# Syno_Ver1.net
KiCad netlist of a schematic drawn in EAGLE
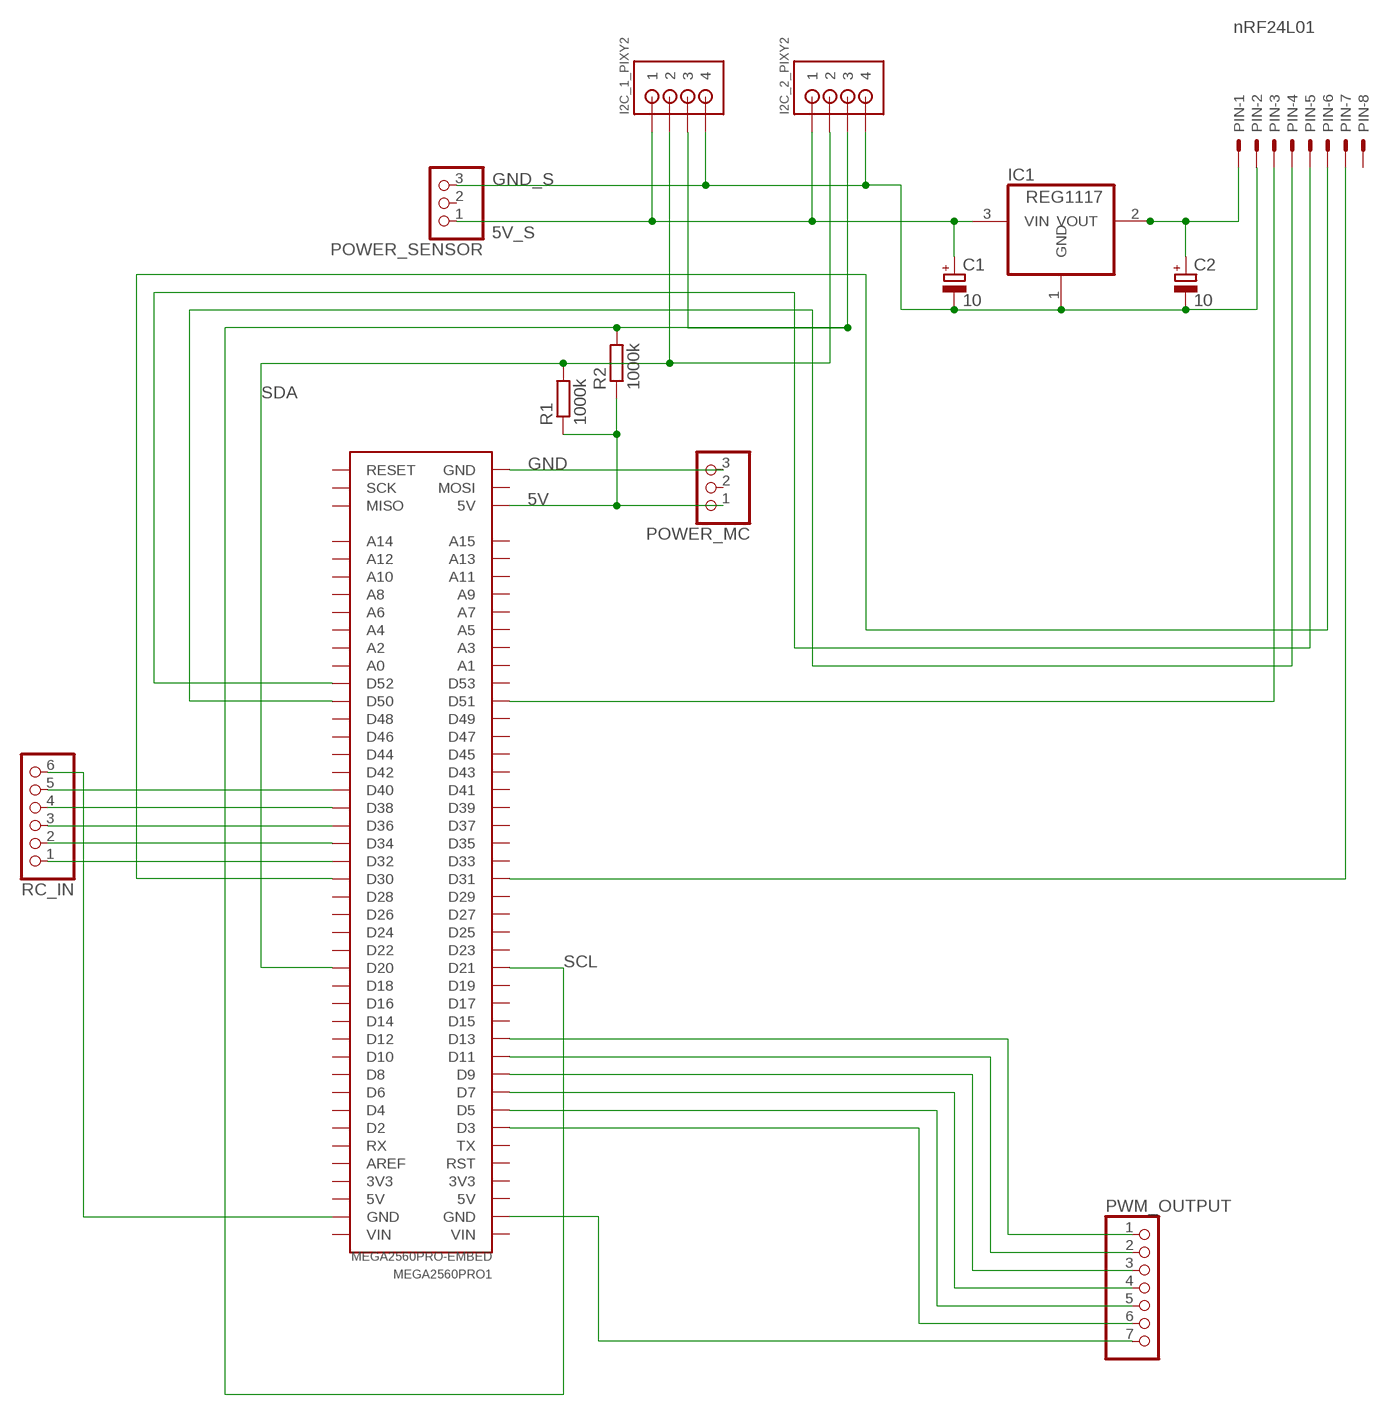
[diagram p0: schematic, sheet 1]

(export (version "E")
  (design (tool "Eeschema 10.0.6"))
  (components
    (comp (ref "C1")
      (value "10")
      (footprint "eagle-import:E1,8-4")
      (libsource (lib "eagle-import") (part "CPOL-EUE1.8-4"))
    )
    (comp (ref "C2")
      (value "10")
      (footprint "eagle-import:E1,8-4")
      (libsource (lib "eagle-import") (part "CPOL-EUE1.8-4"))
    )
    (comp (ref "I2C_1_PIXY2")
      (value "JST-PH_4-PIN_HEADER")
      (footprint "eagle-import:JST_B4B-PH_HEADER")
      (libsource (lib "eagle-import") (part "JST-PH_4-PIN_HEADER"))
    )
    (comp (ref "I2C_2_PIXY2")
      (value "JST-PH_4-PIN_HEADER")
      (footprint "eagle-import:JST_B4B-PH_HEADER")
      (libsource (lib "eagle-import") (part "JST-PH_4-PIN_HEADER"))
    )
    (comp (ref "IC1")
      (value "REG1117")
      (footprint "eagle-import:SOT223")
      (libsource (lib "eagle-import") (part "REG1117"))
    )
    (comp (ref "MEGA2560PRO1")
      (value "MEGA2560PRO-EMBED")
      (footprint "eagle-import:MEGA2560PRO-EMBED")
      (libsource (lib "eagle-import") (part "MEGA2560PRO-EMBED"))
    )
    (comp (ref "PIN")
      (value "nRF24L01")
      (footprint "eagle-import:JST-XH-08-PACKAGE-ROUND-PAD")
      (libsource (lib "eagle-import") (part "JST-XH-08-PIN-ROUND-PAD"))
    )
    (comp (ref "POWER_MC")
      (value "PINHD-1X3/90")
      (footprint "eagle-import:1X03_90")
      (libsource (lib "eagle-import") (part "PINHD-1X3/90"))
    )
    (comp (ref "POWER_SENSOR")
      (value "PINHD-1X3/90")
      (footprint "eagle-import:1X03_90")
      (libsource (lib "eagle-import") (part "PINHD-1X3/90"))
    )
    (comp (ref "PWM_OUTPUT")
      (value "PINHD-1X7/90")
      (footprint "eagle-import:1X07_90")
      (libsource (lib "eagle-import") (part "PINHD-1X7/90"))
    )
    (comp (ref "R1")
      (value "1000k")
      (footprint "eagle-import:0204_5")
      (libsource (lib "eagle-import") (part "R-EU_0204/5"))
    )
    (comp (ref "R2")
      (value "1000k")
      (footprint "eagle-import:0204_5")
      (libsource (lib "eagle-import") (part "R-EU_0204/5"))
    )
    (comp (ref "RC_IN")
      (value "PINHD-1X6/90")
      (footprint "eagle-import:1X06_90")
      (libsource (lib "eagle-import") (part "PINHD-1X6/90"))
    )
  )
  (nets
    (net (code "1") (name "/5V") (class "Default")
      (node (ref "MEGA2560PRO1") (pin "5V@3") (pinfunction "5V_5V@3") (pintype "bidirectional"))
      (node (ref "POWER_MC") (pin "1") (pinfunction "1_1") (pintype "passive"))
      (node (ref "R1") (pin "1") (pinfunction "1_1") (pintype "passive"))
      (node (ref "R2") (pin "1") (pinfunction "1_1") (pintype "passive"))
    )
    (net (code "2") (name "/5V_S") (class "Default")
      (node (ref "C1") (pin "+") (pinfunction "+_+") (pintype "passive"))
      (node (ref "I2C_1_PIXY2") (pin "P1") (pinfunction "1_P1") (pintype "bidirectional"))
      (node (ref "I2C_2_PIXY2") (pin "P1") (pinfunction "1_P1") (pintype "bidirectional"))
      (node (ref "IC1") (pin "3") (pinfunction "VIN_3") (pintype "input"))
      (node (ref "POWER_SENSOR") (pin "1") (pinfunction "1_1") (pintype "passive"))
    )
    (net (code "3") (name "/GND") (class "Default")
      (node (ref "MEGA2560PRO1") (pin "GND@3") (pinfunction "GND_GND@3") (pintype "bidirectional"))
      (node (ref "POWER_MC") (pin "3") (pinfunction "3_3") (pintype "passive"))
    )
    (net (code "4") (name "/GND_S") (class "Default")
      (node (ref "C1") (pin "-") (pinfunction "-_-") (pintype "passive"))
      (node (ref "C2") (pin "-") (pinfunction "-_-") (pintype "passive"))
      (node (ref "I2C_1_PIXY2") (pin "P4") (pinfunction "4_P4") (pintype "bidirectional"))
      (node (ref "I2C_2_PIXY2") (pin "P4") (pinfunction "4_P4") (pintype "bidirectional"))
      (node (ref "IC1") (pin "1") (pinfunction "GND_1") (pintype "power_in"))
      (node (ref "PIN") (pin "2") (pinfunction "S_2") (pintype "passive"))
      (node (ref "POWER_SENSOR") (pin "3") (pinfunction "3_3") (pintype "passive"))
    )
    (net (code "5") (name "/SCL") (class "Default")
      (node (ref "I2C_1_PIXY2") (pin "P3") (pinfunction "3_P3") (pintype "bidirectional"))
      (node (ref "I2C_2_PIXY2") (pin "P3") (pinfunction "3_P3") (pintype "bidirectional"))
      (node (ref "MEGA2560PRO1") (pin "D21") (pinfunction "D21_D21") (pintype "bidirectional"))
      (node (ref "R2") (pin "2") (pinfunction "2_2") (pintype "passive"))
    )
    (net (code "6") (name "/SDA") (class "Default")
      (node (ref "I2C_1_PIXY2") (pin "P2") (pinfunction "2_P2") (pintype "bidirectional"))
      (node (ref "I2C_2_PIXY2") (pin "P2") (pinfunction "2_P2") (pintype "bidirectional"))
      (node (ref "MEGA2560PRO1") (pin "D20") (pinfunction "D20_D20") (pintype "bidirectional"))
      (node (ref "R1") (pin "2") (pinfunction "2_2") (pintype "passive"))
    )
    (net (code "7") (name "Net-(IC1-VOUT)") (class "Default")
      (node (ref "C2") (pin "+") (pinfunction "+_+") (pintype "passive"))
      (node (ref "IC1") (pin "2") (pinfunction "VOUT_2") (pintype "output"))
      (node (ref "PIN") (pin "1") (pinfunction "S_1") (pintype "passive"))
    )
    (net (code "8") (name "Net-(MEGA2560PRO1-GND-PadGND@1)") (class "Default")
      (node (ref "MEGA2560PRO1") (pin "GND@1") (pinfunction "GND_GND@1") (pintype "bidirectional"))
      (node (ref "PWM_OUTPUT") (pin "7") (pinfunction "7_7") (pintype "passive"))
    )
    (net (code "9") (name "Net-(MEGA2560PRO1-GND-PadGND@2)") (class "Default")
      (node (ref "MEGA2560PRO1") (pin "GND@2") (pinfunction "GND_GND@2") (pintype "bidirectional"))
      (node (ref "RC_IN") (pin "6") (pinfunction "6_6") (pintype "passive"))
    )
    (net (code "10") (name "Net-(MEGA2560PRO1-PadD3)") (class "Default")
      (node (ref "MEGA2560PRO1") (pin "D3") (pinfunction "D3_D3") (pintype "bidirectional"))
      (node (ref "PWM_OUTPUT") (pin "6") (pinfunction "6_6") (pintype "passive"))
    )
    (net (code "11") (name "Net-(MEGA2560PRO1-PadD5)") (class "Default")
      (node (ref "MEGA2560PRO1") (pin "D5") (pinfunction "D5_D5") (pintype "bidirectional"))
      (node (ref "PWM_OUTPUT") (pin "5") (pinfunction "5_5") (pintype "passive"))
    )
    (net (code "12") (name "Net-(MEGA2560PRO1-PadD7)") (class "Default")
      (node (ref "MEGA2560PRO1") (pin "D7") (pinfunction "D7_D7") (pintype "bidirectional"))
      (node (ref "PWM_OUTPUT") (pin "4") (pinfunction "4_4") (pintype "passive"))
    )
    (net (code "13") (name "Net-(MEGA2560PRO1-PadD9)") (class "Default")
      (node (ref "MEGA2560PRO1") (pin "D9") (pinfunction "D9_D9") (pintype "bidirectional"))
      (node (ref "PWM_OUTPUT") (pin "3") (pinfunction "3_3") (pintype "passive"))
    )
    (net (code "14") (name "Net-(MEGA2560PRO1-PadD11)") (class "Default")
      (node (ref "MEGA2560PRO1") (pin "D11") (pinfunction "D11_D11") (pintype "bidirectional"))
      (node (ref "PWM_OUTPUT") (pin "2") (pinfunction "2_2") (pintype "passive"))
    )
    (net (code "15") (name "Net-(MEGA2560PRO1-PadD13)") (class "Default")
      (node (ref "MEGA2560PRO1") (pin "D13") (pinfunction "D13_D13") (pintype "bidirectional"))
      (node (ref "PWM_OUTPUT") (pin "1") (pinfunction "1_1") (pintype "passive"))
    )
    (net (code "16") (name "Net-(MEGA2560PRO1-PadD32)") (class "Default")
      (node (ref "MEGA2560PRO1") (pin "D32") (pinfunction "D32_D32") (pintype "bidirectional"))
      (node (ref "RC_IN") (pin "1") (pinfunction "1_1") (pintype "passive"))
    )
    (net (code "17") (name "Net-(MEGA2560PRO1-PadD34)") (class "Default")
      (node (ref "MEGA2560PRO1") (pin "D34") (pinfunction "D34_D34") (pintype "bidirectional"))
      (node (ref "RC_IN") (pin "2") (pinfunction "2_2") (pintype "passive"))
    )
    (net (code "18") (name "Net-(MEGA2560PRO1-PadD36)") (class "Default")
      (node (ref "MEGA2560PRO1") (pin "D36") (pinfunction "D36_D36") (pintype "bidirectional"))
      (node (ref "RC_IN") (pin "3") (pinfunction "3_3") (pintype "passive"))
    )
    (net (code "19") (name "Net-(MEGA2560PRO1-PadD38)") (class "Default")
      (node (ref "MEGA2560PRO1") (pin "D38") (pinfunction "D38_D38") (pintype "bidirectional"))
      (node (ref "RC_IN") (pin "4") (pinfunction "4_4") (pintype "passive"))
    )
    (net (code "20") (name "Net-(MEGA2560PRO1-PadD40)") (class "Default")
      (node (ref "MEGA2560PRO1") (pin "D40") (pinfunction "D40_D40") (pintype "bidirectional"))
      (node (ref "RC_IN") (pin "5") (pinfunction "5_5") (pintype "passive"))
    )
    (net (code "21") (name "Net-(PINC-S)") (class "Default")
      (node (ref "MEGA2560PRO1") (pin "D51") (pinfunction "D51_D51") (pintype "bidirectional"))
      (node (ref "PIN") (pin "3") (pinfunction "S_3") (pintype "passive"))
    )
    (net (code "22") (name "Net-(PIND-S)") (class "Default")
      (node (ref "MEGA2560PRO1") (pin "D50") (pinfunction "D50_D50") (pintype "bidirectional"))
      (node (ref "PIN") (pin "4") (pinfunction "S_4") (pintype "passive"))
    )
    (net (code "23") (name "Net-(PINE-S)") (class "Default")
      (node (ref "MEGA2560PRO1") (pin "D52") (pinfunction "D52_D52") (pintype "bidirectional"))
      (node (ref "PIN") (pin "5") (pinfunction "S_5") (pintype "passive"))
    )
    (net (code "24") (name "Net-(PINF-S)") (class "Default")
      (node (ref "MEGA2560PRO1") (pin "D30") (pinfunction "D30_D30") (pintype "bidirectional"))
      (node (ref "PIN") (pin "6") (pinfunction "S_6") (pintype "passive"))
    )
    (net (code "25") (name "Net-(PING-S)") (class "Default")
      (node (ref "MEGA2560PRO1") (pin "D31") (pinfunction "D31_D31") (pintype "bidirectional"))
      (node (ref "PIN") (pin "7") (pinfunction "S_7") (pintype "passive"))
    )
    (net (code "26") (name "unconnected-(MEGA2560PRO1-3V3-Pad3V3@1)") (class "Default")
      (node (ref "MEGA2560PRO1") (pin "3V3@1") (pinfunction "3V3_3V3@1") (pintype "bidirectional"))
    )
    (net (code "27") (name "unconnected-(MEGA2560PRO1-3V3-Pad3V3@2)") (class "Default")
      (node (ref "MEGA2560PRO1") (pin "3V3@2") (pinfunction "3V3_3V3@2") (pintype "bidirectional"))
    )
    (net (code "28") (name "unconnected-(MEGA2560PRO1-5V-Pad5V@1)") (class "Default")
      (node (ref "MEGA2560PRO1") (pin "5V@1") (pinfunction "5V_5V@1") (pintype "bidirectional"))
    )
    (net (code "29") (name "unconnected-(MEGA2560PRO1-5V-Pad5V@2)") (class "Default")
      (node (ref "MEGA2560PRO1") (pin "5V@2") (pinfunction "5V_5V@2") (pintype "bidirectional"))
    )
    (net (code "30") (name "unconnected-(MEGA2560PRO1-PadA0)") (class "Default")
      (node (ref "MEGA2560PRO1") (pin "A0") (pinfunction "A0_A0") (pintype "bidirectional"))
    )
    (net (code "31") (name "unconnected-(MEGA2560PRO1-PadA1)") (class "Default")
      (node (ref "MEGA2560PRO1") (pin "A1") (pinfunction "A1_A1") (pintype "bidirectional"))
    )
    (net (code "32") (name "unconnected-(MEGA2560PRO1-PadA2)") (class "Default")
      (node (ref "MEGA2560PRO1") (pin "A2") (pinfunction "A2_A2") (pintype "bidirectional"))
    )
    (net (code "33") (name "unconnected-(MEGA2560PRO1-PadA3)") (class "Default")
      (node (ref "MEGA2560PRO1") (pin "A3") (pinfunction "A3_A3") (pintype "bidirectional"))
    )
    (net (code "34") (name "unconnected-(MEGA2560PRO1-PadA4)") (class "Default")
      (node (ref "MEGA2560PRO1") (pin "A4") (pinfunction "A4_A4") (pintype "bidirectional"))
    )
    (net (code "35") (name "unconnected-(MEGA2560PRO1-PadA5)") (class "Default")
      (node (ref "MEGA2560PRO1") (pin "A5") (pinfunction "A5_A5") (pintype "bidirectional"))
    )
    (net (code "36") (name "unconnected-(MEGA2560PRO1-PadA6)") (class "Default")
      (node (ref "MEGA2560PRO1") (pin "A6") (pinfunction "A6_A6") (pintype "bidirectional"))
    )
    (net (code "37") (name "unconnected-(MEGA2560PRO1-PadA7)") (class "Default")
      (node (ref "MEGA2560PRO1") (pin "A7") (pinfunction "A7_A7") (pintype "bidirectional"))
    )
    (net (code "38") (name "unconnected-(MEGA2560PRO1-PadA8)") (class "Default")
      (node (ref "MEGA2560PRO1") (pin "A8") (pinfunction "A8_A8") (pintype "bidirectional"))
    )
    (net (code "39") (name "unconnected-(MEGA2560PRO1-PadA9)") (class "Default")
      (node (ref "MEGA2560PRO1") (pin "A9") (pinfunction "A9_A9") (pintype "bidirectional"))
    )
    (net (code "40") (name "unconnected-(MEGA2560PRO1-PadA10)") (class "Default")
      (node (ref "MEGA2560PRO1") (pin "A10") (pinfunction "A10_A10") (pintype "bidirectional"))
    )
    (net (code "41") (name "unconnected-(MEGA2560PRO1-PadA11)") (class "Default")
      (node (ref "MEGA2560PRO1") (pin "A11") (pinfunction "A11_A11") (pintype "bidirectional"))
    )
    (net (code "42") (name "unconnected-(MEGA2560PRO1-PadA12)") (class "Default")
      (node (ref "MEGA2560PRO1") (pin "A12") (pinfunction "A12_A12") (pintype "bidirectional"))
    )
    (net (code "43") (name "unconnected-(MEGA2560PRO1-PadA13)") (class "Default")
      (node (ref "MEGA2560PRO1") (pin "A13") (pinfunction "A13_A13") (pintype "bidirectional"))
    )
    (net (code "44") (name "unconnected-(MEGA2560PRO1-PadA14)") (class "Default")
      (node (ref "MEGA2560PRO1") (pin "A14") (pinfunction "A14_A14") (pintype "bidirectional"))
    )
    (net (code "45") (name "unconnected-(MEGA2560PRO1-PadA15)") (class "Default")
      (node (ref "MEGA2560PRO1") (pin "A15") (pinfunction "A15_A15") (pintype "bidirectional"))
    )
    (net (code "46") (name "unconnected-(MEGA2560PRO1-PadAREF)") (class "Default")
      (node (ref "MEGA2560PRO1") (pin "AREF") (pinfunction "AREF_AREF") (pintype "bidirectional"))
    )
    (net (code "47") (name "unconnected-(MEGA2560PRO1-PadD2)") (class "Default")
      (node (ref "MEGA2560PRO1") (pin "D2") (pinfunction "D2_D2") (pintype "bidirectional"))
    )
    (net (code "48") (name "unconnected-(MEGA2560PRO1-PadD4)") (class "Default")
      (node (ref "MEGA2560PRO1") (pin "D4") (pinfunction "D4_D4") (pintype "bidirectional"))
    )
    (net (code "49") (name "unconnected-(MEGA2560PRO1-PadD6)") (class "Default")
      (node (ref "MEGA2560PRO1") (pin "D6") (pinfunction "D6_D6") (pintype "bidirectional"))
    )
    (net (code "50") (name "unconnected-(MEGA2560PRO1-PadD8)") (class "Default")
      (node (ref "MEGA2560PRO1") (pin "D8") (pinfunction "D8_D8") (pintype "bidirectional"))
    )
    (net (code "51") (name "unconnected-(MEGA2560PRO1-PadD10)") (class "Default")
      (node (ref "MEGA2560PRO1") (pin "D10") (pinfunction "D10_D10") (pintype "bidirectional"))
    )
    (net (code "52") (name "unconnected-(MEGA2560PRO1-PadD12)") (class "Default")
      (node (ref "MEGA2560PRO1") (pin "D12") (pinfunction "D12_D12") (pintype "bidirectional"))
    )
    (net (code "53") (name "unconnected-(MEGA2560PRO1-PadD14)") (class "Default")
      (node (ref "MEGA2560PRO1") (pin "D14") (pinfunction "D14_D14") (pintype "bidirectional"))
    )
    (net (code "54") (name "unconnected-(MEGA2560PRO1-PadD15)") (class "Default")
      (node (ref "MEGA2560PRO1") (pin "D15") (pinfunction "D15_D15") (pintype "bidirectional"))
    )
    (net (code "55") (name "unconnected-(MEGA2560PRO1-PadD16)") (class "Default")
      (node (ref "MEGA2560PRO1") (pin "D16") (pinfunction "D16_D16") (pintype "bidirectional"))
    )
    (net (code "56") (name "unconnected-(MEGA2560PRO1-PadD17)") (class "Default")
      (node (ref "MEGA2560PRO1") (pin "D17") (pinfunction "D17_D17") (pintype "bidirectional"))
    )
    (net (code "57") (name "unconnected-(MEGA2560PRO1-PadD18)") (class "Default")
      (node (ref "MEGA2560PRO1") (pin "D18") (pinfunction "D18_D18") (pintype "bidirectional"))
    )
    (net (code "58") (name "unconnected-(MEGA2560PRO1-PadD19)") (class "Default")
      (node (ref "MEGA2560PRO1") (pin "D19") (pinfunction "D19_D19") (pintype "bidirectional"))
    )
    (net (code "59") (name "unconnected-(MEGA2560PRO1-PadD22)") (class "Default")
      (node (ref "MEGA2560PRO1") (pin "D22") (pinfunction "D22_D22") (pintype "bidirectional"))
    )
    (net (code "60") (name "unconnected-(MEGA2560PRO1-PadD23)") (class "Default")
      (node (ref "MEGA2560PRO1") (pin "D23") (pinfunction "D23_D23") (pintype "bidirectional"))
    )
    (net (code "61") (name "unconnected-(MEGA2560PRO1-PadD24)") (class "Default")
      (node (ref "MEGA2560PRO1") (pin "D24") (pinfunction "D24_D24") (pintype "bidirectional"))
    )
    (net (code "62") (name "unconnected-(MEGA2560PRO1-PadD25)") (class "Default")
      (node (ref "MEGA2560PRO1") (pin "D25") (pinfunction "D25_D25") (pintype "bidirectional"))
    )
    (net (code "63") (name "unconnected-(MEGA2560PRO1-PadD26)") (class "Default")
      (node (ref "MEGA2560PRO1") (pin "D26") (pinfunction "D26_D26") (pintype "bidirectional"))
    )
    (net (code "64") (name "unconnected-(MEGA2560PRO1-PadD27)") (class "Default")
      (node (ref "MEGA2560PRO1") (pin "D27") (pinfunction "D27_D27") (pintype "bidirectional"))
    )
    (net (code "65") (name "unconnected-(MEGA2560PRO1-PadD28)") (class "Default")
      (node (ref "MEGA2560PRO1") (pin "D28") (pinfunction "D28_D28") (pintype "bidirectional"))
    )
    (net (code "66") (name "unconnected-(MEGA2560PRO1-PadD29)") (class "Default")
      (node (ref "MEGA2560PRO1") (pin "D29") (pinfunction "D29_D29") (pintype "bidirectional"))
    )
    (net (code "67") (name "unconnected-(MEGA2560PRO1-PadD33)") (class "Default")
      (node (ref "MEGA2560PRO1") (pin "D33") (pinfunction "D33_D33") (pintype "bidirectional"))
    )
    (net (code "68") (name "unconnected-(MEGA2560PRO1-PadD35)") (class "Default")
      (node (ref "MEGA2560PRO1") (pin "D35") (pinfunction "D35_D35") (pintype "bidirectional"))
    )
    (net (code "69") (name "unconnected-(MEGA2560PRO1-PadD37)") (class "Default")
      (node (ref "MEGA2560PRO1") (pin "D37") (pinfunction "D37_D37") (pintype "bidirectional"))
    )
    (net (code "70") (name "unconnected-(MEGA2560PRO1-PadD39)") (class "Default")
      (node (ref "MEGA2560PRO1") (pin "D39") (pinfunction "D39_D39") (pintype "bidirectional"))
    )
    (net (code "71") (name "unconnected-(MEGA2560PRO1-PadD41)") (class "Default")
      (node (ref "MEGA2560PRO1") (pin "D41") (pinfunction "D41_D41") (pintype "bidirectional"))
    )
    (net (code "72") (name "unconnected-(MEGA2560PRO1-PadD42)") (class "Default")
      (node (ref "MEGA2560PRO1") (pin "D42") (pinfunction "D42_D42") (pintype "bidirectional"))
    )
    (net (code "73") (name "unconnected-(MEGA2560PRO1-PadD43)") (class "Default")
      (node (ref "MEGA2560PRO1") (pin "D43") (pinfunction "D43_D43") (pintype "bidirectional"))
    )
    (net (code "74") (name "unconnected-(MEGA2560PRO1-PadD44)") (class "Default")
      (node (ref "MEGA2560PRO1") (pin "D44") (pinfunction "D44_D44") (pintype "bidirectional"))
    )
    (net (code "75") (name "unconnected-(MEGA2560PRO1-PadD45)") (class "Default")
      (node (ref "MEGA2560PRO1") (pin "D45") (pinfunction "D45_D45") (pintype "bidirectional"))
    )
    (net (code "76") (name "unconnected-(MEGA2560PRO1-PadD46)") (class "Default")
      (node (ref "MEGA2560PRO1") (pin "D46") (pinfunction "D46_D46") (pintype "bidirectional"))
    )
    (net (code "77") (name "unconnected-(MEGA2560PRO1-PadD47)") (class "Default")
      (node (ref "MEGA2560PRO1") (pin "D47") (pinfunction "D47_D47") (pintype "bidirectional"))
    )
    (net (code "78") (name "unconnected-(MEGA2560PRO1-PadD48)") (class "Default")
      (node (ref "MEGA2560PRO1") (pin "D48") (pinfunction "D48_D48") (pintype "bidirectional"))
    )
    (net (code "79") (name "unconnected-(MEGA2560PRO1-PadD49)") (class "Default")
      (node (ref "MEGA2560PRO1") (pin "D49") (pinfunction "D49_D49") (pintype "bidirectional"))
    )
    (net (code "80") (name "unconnected-(MEGA2560PRO1-PadD53)") (class "Default")
      (node (ref "MEGA2560PRO1") (pin "D53") (pinfunction "D53_D53") (pintype "bidirectional"))
    )
    (net (code "81") (name "unconnected-(MEGA2560PRO1-PadMISO)") (class "Default")
      (node (ref "MEGA2560PRO1") (pin "MISO") (pinfunction "MISO_MISO") (pintype "bidirectional"))
    )
    (net (code "82") (name "unconnected-(MEGA2560PRO1-PadMOSI)") (class "Default")
      (node (ref "MEGA2560PRO1") (pin "MOSI") (pinfunction "MOSI_MOSI") (pintype "bidirectional"))
    )
    (net (code "83") (name "unconnected-(MEGA2560PRO1-PadRESET)") (class "Default")
      (node (ref "MEGA2560PRO1") (pin "RESET") (pinfunction "RESET_RESET") (pintype "bidirectional"))
    )
    (net (code "84") (name "unconnected-(MEGA2560PRO1-PadRST)") (class "Default")
      (node (ref "MEGA2560PRO1") (pin "RST") (pinfunction "RST_RST") (pintype "bidirectional"))
    )
    (net (code "85") (name "unconnected-(MEGA2560PRO1-PadRX)") (class "Default")
      (node (ref "MEGA2560PRO1") (pin "RX") (pinfunction "RX_RX") (pintype "bidirectional"))
    )
    (net (code "86") (name "unconnected-(MEGA2560PRO1-PadSCK)") (class "Default")
      (node (ref "MEGA2560PRO1") (pin "SCK") (pinfunction "SCK_SCK") (pintype "bidirectional"))
    )
    (net (code "87") (name "unconnected-(MEGA2560PRO1-PadTX)") (class "Default")
      (node (ref "MEGA2560PRO1") (pin "TX") (pinfunction "TX_TX") (pintype "bidirectional"))
    )
    (net (code "88") (name "unconnected-(MEGA2560PRO1-VIN-PadVIN@1)") (class "Default")
      (node (ref "MEGA2560PRO1") (pin "VIN@1") (pinfunction "VIN_VIN@1") (pintype "bidirectional"))
    )
    (net (code "89") (name "unconnected-(MEGA2560PRO1-VIN-PadVIN@2)") (class "Default")
      (node (ref "MEGA2560PRO1") (pin "VIN@2") (pinfunction "VIN_VIN@2") (pintype "bidirectional"))
    )
    (net (code "90") (name "unconnected-(PINH-S-Pad8)") (class "Default")
      (node (ref "PIN") (pin "8") (pinfunction "S_8") (pintype "passive"))
    )
    (net (code "91") (name "unconnected-(POWER_MC-Pad2)") (class "Default")
      (node (ref "POWER_MC") (pin "2") (pinfunction "2_2") (pintype "passive"))
    )
    (net (code "92") (name "unconnected-(POWER_SENSOR-Pad2)") (class "Default")
      (node (ref "POWER_SENSOR") (pin "2") (pinfunction "2_2") (pintype "passive"))
    )
  )
)
